# Led_Driver.net
KiCad netlist of a schematic drawn in Altium Designer
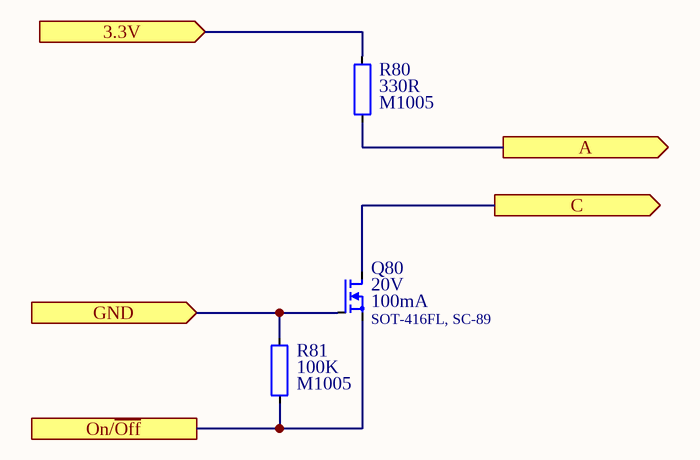
[diagram p0: Led Driver.SchDoc]

(export (version "E")
  (design (tool "Eeschema 10.0.6"))
  (components
    (comp (ref "Q80")
      (value "Mosfet, N-Channel")
      (footprint "SOT-416FL, Mosfet - Type 1")
      (description "MOSFET, N-CH, 20V, 100mA, SOT-416FL")
      (fields
        (field (name "MANUFACTURER PART NUMBER") "RE1C001UNTCL")
        (field (name "MANUFACTURER") "Rohm")
        (field (name "CURRENT") "100mA")
        (field (name "VOLTAGE") "20V")
        (field (name "PACKAGE") "SOT-416FL, SC-89")
      )
      (libsource (lib "Transistor") (part "Mosfet, N-Channel"))
    )
    (comp (ref "R80")
      (value "330R")
      (footprint "Resistor_Smd_M1005_I0402")
      (description "Res, 330R, 1%, M1005")
      (fields
        (field (name "TOLERANCE") "1%")
        (field (name "MANUFACTURER") "Yageo")
        (field (name "PACKAGE") "M1005")
      )
      (libsource (lib "Resistor") (part "Resistor"))
    )
    (comp (ref "R81")
      (value "100K")
      (footprint "Resistor_Smd_M1005_I0402")
      (description "Res, 100K, 1%, M1005")
      (fields
        (field (name "TOLERANCE") "1%")
        (field (name "MANUFACTURER") "Yageo")
        (field (name "PACKAGE") "M1005")
      )
      (libsource (lib "Resistor") (part "Resistor"))
    )
  )
  (nets
    (net (code "1") (name "/3.3V") (class "Default")
      (node (ref "R80") (pin "1") (pinfunction "1_1") (pintype "passive"))
    )
    (net (code "2") (name "/A") (class "Default")
      (node (ref "R80") (pin "2") (pinfunction "2_2") (pintype "passive"))
    )
    (net (code "3") (name "/C") (class "Default")
      (node (ref "Q80") (pin "D") (pinfunction "D_D") (pintype "passive"))
    )
    (net (code "4") (name "/GND") (class "Default")
      (node (ref "Q80") (pin "G") (pinfunction "G_G") (pintype "passive"))
      (node (ref "R81") (pin "1") (pinfunction "1_1") (pintype "passive"))
    )
    (net (code "5") (name "/On{slash}~{Off}") (class "Default")
      (node (ref "Q80") (pin "S") (pinfunction "S_S") (pintype "passive"))
      (node (ref "R81") (pin "2") (pinfunction "2_2") (pintype "passive"))
    )
  )
)
